# MCU_-_FLASH.net
KiCad netlist of a schematic drawn in Altium Designer
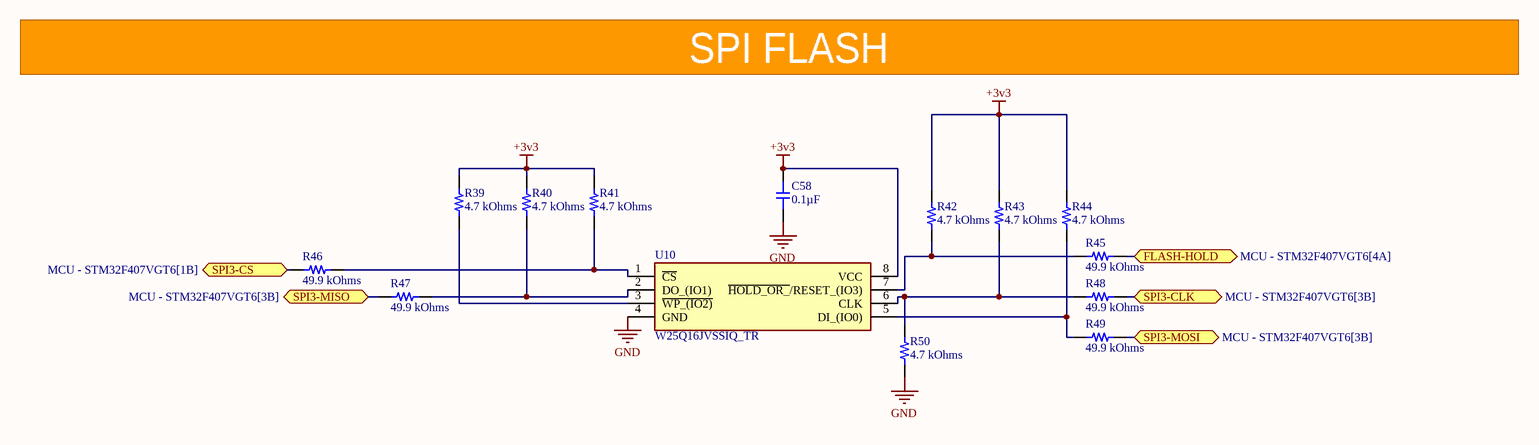
[diagram p0: MCU - FLASH.SchDoc]

(export (version "E")
  (design (tool "Eeschema 10.0.6"))
  (components
    (comp (ref "C58")
      (value "0.1µF")
      (footprint "0603_Footprint")
      (description "0.1uF 0603 Surface Capacitor")
      (libsource (lib "MainLibrary") (part "0.1uF 0603 Surface Capacitor"))
    )
    (comp (ref "R39")
      (value "4.7 kOhms")
      (footprint "0603_RES")
      (description "4.7 kOhms 0603")
      (libsource (lib "MainLibrary") (part "4.7 kOhms 0603"))
    )
    (comp (ref "R40")
      (value "4.7 kOhms")
      (footprint "0603_RES")
      (description "4.7 kOhms 0603")
      (libsource (lib "MainLibrary") (part "4.7 kOhms 0603"))
    )
    (comp (ref "R41")
      (value "4.7 kOhms")
      (footprint "0603_RES")
      (description "4.7 kOhms 0603")
      (libsource (lib "MainLibrary") (part "4.7 kOhms 0603"))
    )
    (comp (ref "R42")
      (value "4.7 kOhms")
      (footprint "0603_RES")
      (description "4.7 kOhms 0603")
      (libsource (lib "MainLibrary") (part "4.7 kOhms 0603"))
    )
    (comp (ref "R43")
      (value "4.7 kOhms")
      (footprint "0603_RES")
      (description "4.7 kOhms 0603")
      (libsource (lib "MainLibrary") (part "4.7 kOhms 0603"))
    )
    (comp (ref "R44")
      (value "4.7 kOhms")
      (footprint "0603_RES")
      (description "4.7 kOhms 0603")
      (libsource (lib "MainLibrary") (part "4.7 kOhms 0603"))
    )
    (comp (ref "R45")
      (value "49.9 kOhms")
      (footprint "0603_RES")
      (description "49.9 kOhms 0603")
      (libsource (lib "MainLibrary") (part "49.9 kOhms 0603"))
    )
    (comp (ref "R46")
      (value "49.9 kOhms")
      (footprint "0603_RES")
      (description "49.9 kOhms 0603")
      (libsource (lib "MainLibrary") (part "49.9 kOhms 0603"))
    )
    (comp (ref "R47")
      (value "49.9 kOhms")
      (footprint "0603_RES")
      (description "49.9 kOhms 0603")
      (libsource (lib "MainLibrary") (part "49.9 kOhms 0603"))
    )
    (comp (ref "R48")
      (value "49.9 kOhms")
      (footprint "0603_RES")
      (description "49.9 kOhms 0603")
      (libsource (lib "MainLibrary") (part "49.9 kOhms 0603"))
    )
    (comp (ref "R49")
      (value "49.9 kOhms")
      (footprint "0603_RES")
      (description "49.9 kOhms 0603")
      (libsource (lib "MainLibrary") (part "49.9 kOhms 0603"))
    )
    (comp (ref "R50")
      (value "4.7 kOhms")
      (footprint "0603_RES")
      (description "4.7 kOhms 0603")
      (libsource (lib "MainLibrary") (part "4.7 kOhms 0603"))
    )
    (comp (ref "U10")
      (value "W25Q16JVSSIQ_TR")
      (footprint "SOIC127P790X216-8N")
      (description "Integrated Circuit")
      (fields
        (field (name "MANUFACTURER_PART_NUMBER") "W25Q16JVSSIQ TR")
        (field (name "MOUSER PART NUMBER") "454-W25Q16JVSSIQTR")
      )
      (libsource (lib "MainLibrary") (part "W25Q16JVSSIQ_TR"))
    )
  )
  (nets
    (net (code "1") (name "+3v3") (class "Default")
      (node (ref "C58") (pin "1") (pinfunction "1_1") (pintype "passive"))
      (node (ref "R39") (pin "2") (pinfunction "2_2") (pintype "passive"))
      (node (ref "R40") (pin "2") (pinfunction "2_2") (pintype "passive"))
      (node (ref "R41") (pin "2") (pinfunction "2_2") (pintype "passive"))
      (node (ref "R42") (pin "2") (pinfunction "2_2") (pintype "passive"))
      (node (ref "R43") (pin "2") (pinfunction "2_2") (pintype "passive"))
      (node (ref "R44") (pin "2") (pinfunction "2_2") (pintype "passive"))
      (node (ref "U10") (pin "8") (pinfunction "VCC_8") (pintype "passive"))
    )
    (net (code "2") (name "/FLASH-HOLD") (class "Default")
      (node (ref "R45") (pin "2") (pinfunction "2_2") (pintype "passive"))
    )
    (net (code "3") (name "/SPI3-CLK") (class "Default")
      (node (ref "R48") (pin "2") (pinfunction "2_2") (pintype "passive"))
    )
    (net (code "4") (name "/SPI3-CS") (class "Default")
      (node (ref "R46") (pin "1") (pinfunction "1_1") (pintype "passive"))
    )
    (net (code "5") (name "/SPI3-MISO") (class "Default")
      (node (ref "R47") (pin "1") (pinfunction "1_1") (pintype "passive"))
    )
    (net (code "6") (name "/SPI3-MOSI") (class "Default")
      (node (ref "R49") (pin "2") (pinfunction "2_2") (pintype "passive"))
    )
    (net (code "7") (name "GND") (class "Default")
      (node (ref "C58") (pin "2") (pinfunction "2_2") (pintype "passive"))
      (node (ref "R50") (pin "1") (pinfunction "1_1") (pintype "passive"))
      (node (ref "U10") (pin "4") (pinfunction "GND_4") (pintype "passive"))
    )
    (net (code "8") (name "Net-(U10-CLK)") (class "Default")
      (node (ref "R43") (pin "1") (pinfunction "1_1") (pintype "passive"))
      (node (ref "R48") (pin "1") (pinfunction "1_1") (pintype "passive"))
      (node (ref "R50") (pin "2") (pinfunction "2_2") (pintype "passive"))
      (node (ref "U10") (pin "6") (pinfunction "CLK_6") (pintype "passive"))
    )
    (net (code "9") (name "Net-(U10-DI_(IO0))") (class "Default")
      (node (ref "R44") (pin "1") (pinfunction "1_1") (pintype "passive"))
      (node (ref "R49") (pin "1") (pinfunction "1_1") (pintype "passive"))
      (node (ref "U10") (pin "5") (pinfunction "DI_(IO0)_5") (pintype "passive"))
    )
    (net (code "10") (name "Net-(U10-DO_(IO1))") (class "Default")
      (node (ref "R40") (pin "1") (pinfunction "1_1") (pintype "passive"))
      (node (ref "R47") (pin "2") (pinfunction "2_2") (pintype "passive"))
      (node (ref "U10") (pin "2") (pinfunction "DO_(IO1)_2") (pintype "passive"))
    )
    (net (code "11") (name "Net-(U10-~{CS})") (class "Default")
      (node (ref "R41") (pin "1") (pinfunction "1_1") (pintype "passive"))
      (node (ref "R46") (pin "2") (pinfunction "2_2") (pintype "passive"))
      (node (ref "U10") (pin "1") (pinfunction "~{CS}_1") (pintype "passive"))
    )
    (net (code "12") (name "Net-(U10-~{HOLD_OR_}{slash}RESET_(IO3))") (class "Default")
      (node (ref "R42") (pin "1") (pinfunction "1_1") (pintype "passive"))
      (node (ref "R45") (pin "1") (pinfunction "1_1") (pintype "passive"))
      (node (ref "U10") (pin "7") (pinfunction "~{HOLD_OR_}/RESET_(IO3)_7") (pintype "passive"))
    )
    (net (code "13") (name "Net-(U10-~{WP_(IO2)})") (class "Default")
      (node (ref "R39") (pin "1") (pinfunction "1_1") (pintype "passive"))
      (node (ref "U10") (pin "3") (pinfunction "~{WP_(IO2)}_3") (pintype "passive"))
    )
  )
)
